# CargaSecundaria.net
KiCad netlist of a schematic drawn in EAGLE
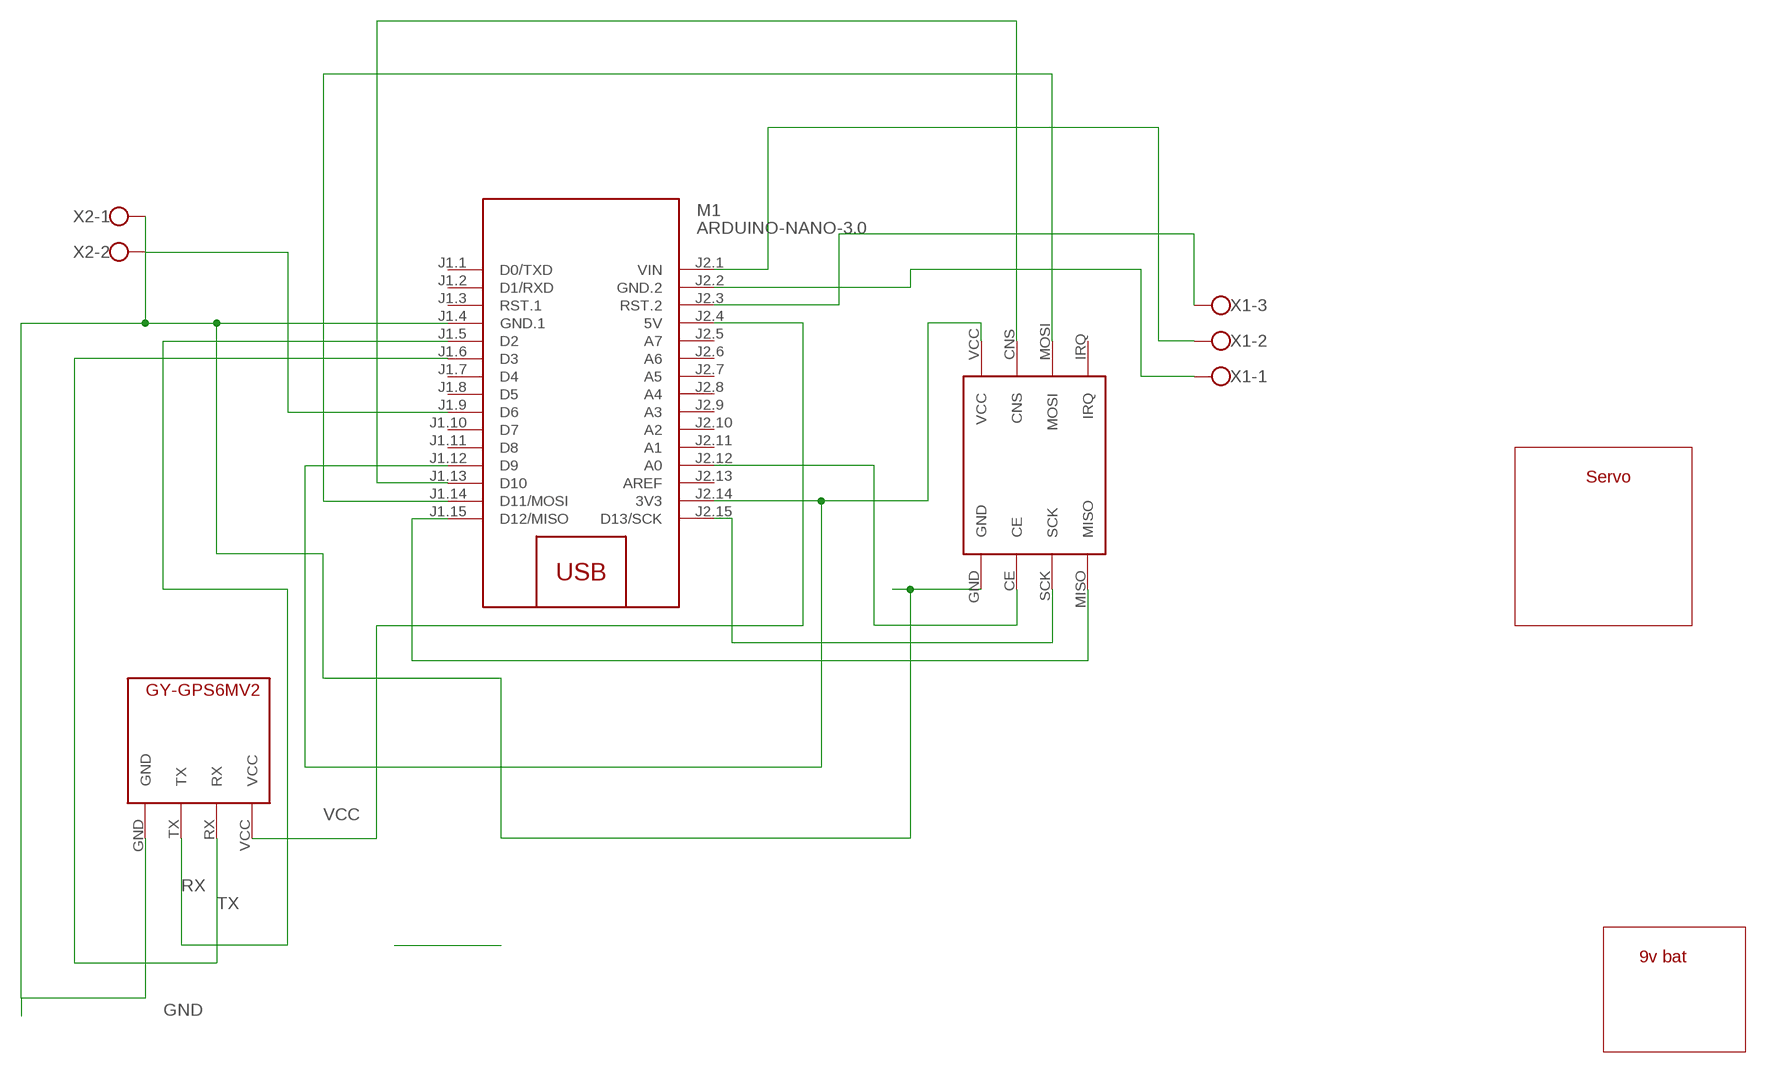
[diagram p0: schematic, sheet 1]

(export (version "E")
  (design (tool "Eeschema 10.0.6"))
  (components
    (comp (ref "M1")
      (value "ARDUINO-NANO-3.0")
      (footprint "eagle-import:ARDUINO-NANO-3.0")
      (libsource (lib "eagle-import") (part "ARDUINO-NANO-3.0"))
    )
    (comp (ref "U$2")
      (value "SERVO_DEVICE")
      (footprint "eagle-import:SERVO_FOOTPRINT")
      (libsource (lib "eagle-import") (part "SERVO_DEVICE"))
    )
    (comp (ref "U$3")
      (value "NRF24L01_DEVICE")
      (footprint "eagle-import:NRF24L01_FOOTPRINT")
      (libsource (lib "eagle-import") (part "NRF24L01_DEVICE"))
    )
    (comp (ref "U$4")
      (value "9VBAT_DEVICE")
      (footprint "eagle-import:9V_FOOTRPRINT")
      (libsource (lib "eagle-import") (part "9VBAT_DEVICE"))
    )
    (comp (ref "U$5")
      (value "GY-GPS6M_VUPDOWMNLIB")
      (footprint "eagle-import:GY-GPS6M_FOOTPRINT_UPSIDEDOWN")
      (libsource (lib "eagle-import") (part "GY-GPS6M_VUPDOWMNLIB"))
    )
    (comp (ref "X1")
      (value "W237-103")
      (footprint "eagle-import:W237-103")
      (fields (field (name "MPN") "237-103"))
      (libsource (lib "eagle-import") (part "W237-103"))
    )
    (comp (ref "X2")
      (value "W237-102")
      (footprint "eagle-import:W237-102")
      (fields (field (name "MPN") "237-102"))
      (libsource (lib "eagle-import") (part "W237-102"))
    )
  )
  (nets
    (net (code "1") (name "/GND") (class "Default")
      (node (ref "M1") (pin "J1.4") (pinfunction "GND.1_J1.4") (pintype "power_in"))
      (node (ref "U$3") (pin "GND") (pinfunction "GND_GND") (pintype "power_in"))
      (node (ref "U$5") (pin "GND") (pinfunction "GND_GND") (pintype "power_in"))
      (node (ref "X2") (pin "1") (pinfunction "KL_1") (pintype "passive"))
    )
    (net (code "2") (name "/RX") (class "Default")
      (node (ref "M1") (pin "J1.5") (pinfunction "D2_J1.5") (pintype "bidirectional"))
      (node (ref "U$5") (pin "TX") (pinfunction "TX_TX") (pintype "bidirectional"))
    )
    (net (code "3") (name "/TX") (class "Default")
      (node (ref "M1") (pin "J1.6") (pinfunction "D3_J1.6") (pintype "bidirectional"))
      (node (ref "U$5") (pin "RX") (pinfunction "RX_RX") (pintype "bidirectional"))
    )
    (net (code "4") (name "/VCC") (class "Default")
      (node (ref "M1") (pin "J2.4") (pinfunction "5V_J2.4") (pintype "power_in"))
      (node (ref "U$5") (pin "VCC") (pinfunction "VCC_VCC") (pintype "power_in"))
    )
    (net (code "5") (name "Net-(M1-3V3)") (class "Default")
      (node (ref "M1") (pin "J1.12") (pinfunction "D9_J1.12") (pintype "bidirectional"))
      (node (ref "M1") (pin "J2.14") (pinfunction "3V3_J2.14") (pintype "power_in"))
      (node (ref "U$3") (pin "VCC") (pinfunction "VCC_VCC") (pintype "power_in"))
    )
    (net (code "6") (name "Net-(M1-A0)") (class "Default")
      (node (ref "M1") (pin "J2.12") (pinfunction "A0_J2.12") (pintype "bidirectional"))
      (node (ref "U$3") (pin "CE") (pinfunction "CE_CE") (pintype "bidirectional"))
    )
    (net (code "7") (name "Net-(M1-D6)") (class "Default")
      (node (ref "M1") (pin "J1.9") (pinfunction "D6_J1.9") (pintype "bidirectional"))
      (node (ref "X2") (pin "2") (pinfunction "KL_2") (pintype "passive"))
    )
    (net (code "8") (name "Net-(M1-D10)") (class "Default")
      (node (ref "M1") (pin "J1.13") (pinfunction "D10_J1.13") (pintype "bidirectional"))
      (node (ref "U$3") (pin "CNS") (pinfunction "CNS_CNS") (pintype "bidirectional"))
    )
    (net (code "9") (name "Net-(M1-D11{slash}MOSI)") (class "Default")
      (node (ref "M1") (pin "J1.14") (pinfunction "D11/MOSI_J1.14") (pintype "bidirectional"))
      (node (ref "U$3") (pin "MOSI") (pinfunction "MOSI_MOSI") (pintype "bidirectional"))
    )
    (net (code "10") (name "Net-(M1-D12{slash}MISO)") (class "Default")
      (node (ref "M1") (pin "J1.15") (pinfunction "D12/MISO_J1.15") (pintype "bidirectional"))
      (node (ref "U$3") (pin "MISO") (pinfunction "MISO_MISO") (pintype "bidirectional"))
    )
    (net (code "11") (name "Net-(M1-D13{slash}SCK)") (class "Default")
      (node (ref "M1") (pin "J2.15") (pinfunction "D13/SCK_J2.15") (pintype "bidirectional"))
      (node (ref "U$3") (pin "SCK") (pinfunction "SCK_SCK") (pintype "bidirectional"))
    )
    (net (code "12") (name "Net-(M1-GND.2)") (class "Default")
      (node (ref "M1") (pin "J2.2") (pinfunction "GND.2_J2.2") (pintype "power_in"))
      (node (ref "X1") (pin "1") (pinfunction "KL_1") (pintype "passive"))
    )
    (net (code "13") (name "Net-(M1-RST.2)") (class "Default")
      (node (ref "M1") (pin "J2.3") (pinfunction "RST.2_J2.3") (pintype "bidirectional"))
      (node (ref "X1") (pin "3") (pinfunction "KL_3") (pintype "passive"))
    )
    (net (code "14") (name "Net-(M1-VIN)") (class "Default")
      (node (ref "M1") (pin "J2.1") (pinfunction "VIN_J2.1") (pintype "power_in"))
      (node (ref "X1") (pin "2") (pinfunction "KL_2") (pintype "passive"))
    )
    (net (code "15") (name "unconnected-(M1-A1-PadJ2.11)") (class "Default")
      (node (ref "M1") (pin "J2.11") (pinfunction "A1_J2.11") (pintype "bidirectional"))
    )
    (net (code "16") (name "unconnected-(M1-A2-PadJ2.10)") (class "Default")
      (node (ref "M1") (pin "J2.10") (pinfunction "A2_J2.10") (pintype "bidirectional"))
    )
    (net (code "17") (name "unconnected-(M1-A3-PadJ2.9)") (class "Default")
      (node (ref "M1") (pin "J2.9") (pinfunction "A3_J2.9") (pintype "bidirectional"))
    )
    (net (code "18") (name "unconnected-(M1-A4-PadJ2.8)") (class "Default")
      (node (ref "M1") (pin "J2.8") (pinfunction "A4_J2.8") (pintype "bidirectional"))
    )
    (net (code "19") (name "unconnected-(M1-A5-PadJ2.7)") (class "Default")
      (node (ref "M1") (pin "J2.7") (pinfunction "A5_J2.7") (pintype "bidirectional"))
    )
    (net (code "20") (name "unconnected-(M1-A6-PadJ2.6)") (class "Default")
      (node (ref "M1") (pin "J2.6") (pinfunction "A6_J2.6") (pintype "bidirectional"))
    )
    (net (code "21") (name "unconnected-(M1-A7-PadJ2.5)") (class "Default")
      (node (ref "M1") (pin "J2.5") (pinfunction "A7_J2.5") (pintype "bidirectional"))
    )
    (net (code "22") (name "unconnected-(M1-AREF-PadJ2.13)") (class "Default")
      (node (ref "M1") (pin "J2.13") (pinfunction "AREF_J2.13") (pintype "bidirectional"))
    )
    (net (code "23") (name "unconnected-(M1-D0{slash}TXD-PadJ1.1)") (class "Default")
      (node (ref "M1") (pin "J1.1") (pinfunction "D0/TXD_J1.1") (pintype "bidirectional"))
    )
    (net (code "24") (name "unconnected-(M1-D1{slash}RXD-PadJ1.2)") (class "Default")
      (node (ref "M1") (pin "J1.2") (pinfunction "D1/RXD_J1.2") (pintype "bidirectional"))
    )
    (net (code "25") (name "unconnected-(M1-D4-PadJ1.7)") (class "Default")
      (node (ref "M1") (pin "J1.7") (pinfunction "D4_J1.7") (pintype "bidirectional"))
    )
    (net (code "26") (name "unconnected-(M1-D5-PadJ1.8)") (class "Default")
      (node (ref "M1") (pin "J1.8") (pinfunction "D5_J1.8") (pintype "bidirectional"))
    )
    (net (code "27") (name "unconnected-(M1-D7-PadJ1.10)") (class "Default")
      (node (ref "M1") (pin "J1.10") (pinfunction "D7_J1.10") (pintype "bidirectional"))
    )
    (net (code "28") (name "unconnected-(M1-D8-PadJ1.11)") (class "Default")
      (node (ref "M1") (pin "J1.11") (pinfunction "D8_J1.11") (pintype "bidirectional"))
    )
    (net (code "29") (name "unconnected-(M1-RST.1-PadJ1.3)") (class "Default")
      (node (ref "M1") (pin "J1.3") (pinfunction "RST.1_J1.3") (pintype "bidirectional"))
    )
    (net (code "30") (name "unconnected-(U$3-PadIRQ)") (class "Default")
      (node (ref "U$3") (pin "IRQ") (pinfunction "IRQ_IRQ") (pintype "bidirectional"))
    )
  )
)
